# antenna.net
KiCad netlist of a schematic drawn in EAGLE
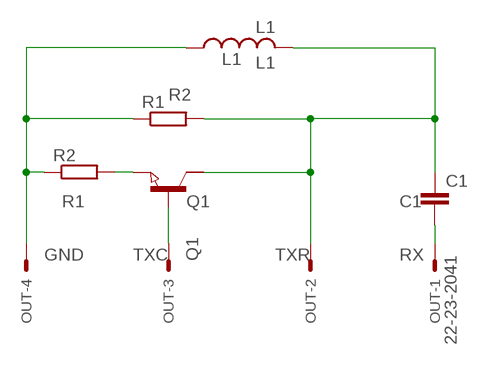
[diagram p0: schematic, sheet 1]

(export (version "E")
  (design (tool "Eeschema 10.0.6"))
  (components
    (comp (ref "C1")
      (value "C2,5-3")
      (footprint "eagle-import:C2.5-3")
      (libsource (lib "eagle-import") (part "C2,5-3"))
    )
    (comp (ref "L1")
      (value "L1")
      (footprint "eagle-import:0204_5")
      (libsource (lib "eagle-import") (part "L-US0204/5"))
    )
    (comp (ref "OUT")
      (value "22-23-2041")
      (footprint "eagle-import:22-23-2041")
      (fields (field (name "MF") "MOLEX"))
      (libsource (lib "eagle-import") (part "22-23-2041"))
    )
    (comp (ref "Q1")
      (value "NPN-TRANSISTIOR-2COLSOT89")
      (footprint "eagle-import:SOT89")
      (libsource (lib "eagle-import") (part "NPN-TRANSISTIOR-2COLSOT89"))
    )
    (comp (ref "R1")
      (value "R-EU_0207/15")
      (footprint "eagle-import:0207_15")
      (libsource (lib "eagle-import") (part "R-EU_0207/15"))
    )
    (comp (ref "R2")
      (value "R-EU_0207/15")
      (footprint "eagle-import:0207_15")
      (libsource (lib "eagle-import") (part "R-EU_0207/15"))
    )
  )
  (nets
    (net (code "1") (name "Net-(OUTA-S)") (class "Default")
      (node (ref "C1") (pin "2") (pinfunction "2_2") (pintype "passive"))
      (node (ref "OUT") (pin "1") (pinfunction "S_1") (pintype "passive"))
    )
    (net (code "2") (name "Net-(OUTB-S)") (class "Default")
      (node (ref "C1") (pin "1") (pinfunction "1_1") (pintype "passive"))
      (node (ref "L1") (pin "2") (pinfunction "2_2") (pintype "passive"))
      (node (ref "OUT") (pin "2") (pinfunction "S_2") (pintype "passive"))
      (node (ref "Q1") (pin "2") (pinfunction "C_2") (pintype "passive"))
      (node (ref "R1") (pin "2") (pinfunction "2_2") (pintype "passive"))
    )
    (net (code "3") (name "Net-(OUTC-S)") (class "Default")
      (node (ref "OUT") (pin "3") (pinfunction "S_3") (pintype "passive"))
      (node (ref "Q1") (pin "1") (pinfunction "B_1") (pintype "passive"))
    )
    (net (code "4") (name "Net-(OUTD-S)") (class "Default")
      (node (ref "L1") (pin "1") (pinfunction "1_1") (pintype "passive"))
      (node (ref "OUT") (pin "4") (pinfunction "S_4") (pintype "passive"))
      (node (ref "R1") (pin "1") (pinfunction "1_1") (pintype "passive"))
      (node (ref "R2") (pin "1") (pinfunction "1_1") (pintype "passive"))
    )
    (net (code "5") (name "Net-(Q1-E)") (class "Default")
      (node (ref "Q1") (pin "3") (pinfunction "E_3") (pintype "passive"))
      (node (ref "R2") (pin "2") (pinfunction "2_2") (pintype "passive"))
    )
    (net (code "6") (name "unconnected-(Q1-C{slash}-Pad2@1)") (class "Default")
      (node (ref "Q1") (pin "2@1") (pinfunction "C/_2@1") (pintype "passive"))
    )
  )
)
